# RC.net
KiCad netlist of a schematic drawn in EAGLE
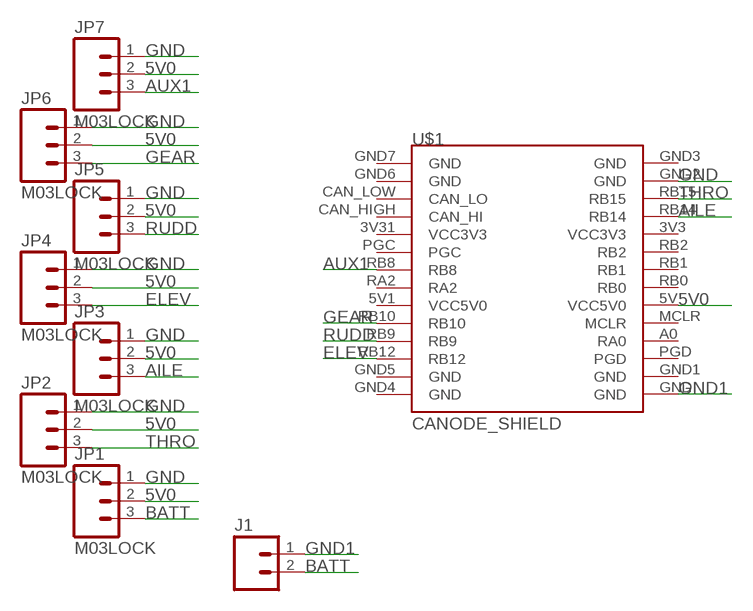
[diagram p0: schematic, sheet 1]

(export (version "E")
  (design (tool "Eeschema 10.0.6"))
  (components
    (comp (ref "J1")
      (value "M02LOCK")
      (footprint "eagle-import:1X02_LOCK")
      (libsource (lib "eagle-import") (part "M02LOCK"))
    )
    (comp (ref "JP1")
      (value "M03LOCK")
      (footprint "eagle-import:1X03_LOCK")
      (libsource (lib "eagle-import") (part "M03LOCK"))
    )
    (comp (ref "JP2")
      (value "M03LOCK")
      (footprint "eagle-import:1X03_LOCK")
      (libsource (lib "eagle-import") (part "M03LOCK"))
    )
    (comp (ref "JP3")
      (value "M03LOCK")
      (footprint "eagle-import:1X03_LOCK")
      (libsource (lib "eagle-import") (part "M03LOCK"))
    )
    (comp (ref "JP4")
      (value "M03LOCK")
      (footprint "eagle-import:1X03_LOCK")
      (libsource (lib "eagle-import") (part "M03LOCK"))
    )
    (comp (ref "JP5")
      (value "M03LOCK")
      (footprint "eagle-import:1X03_LOCK")
      (libsource (lib "eagle-import") (part "M03LOCK"))
    )
    (comp (ref "JP6")
      (value "M03LOCK")
      (footprint "eagle-import:1X03_LOCK")
      (libsource (lib "eagle-import") (part "M03LOCK"))
    )
    (comp (ref "JP7")
      (value "M03LOCK")
      (footprint "eagle-import:1X03_LOCK")
      (libsource (lib "eagle-import") (part "M03LOCK"))
    )
    (comp (ref "U$1")
      (value "CANODE_SHIELD")
      (footprint "eagle-import:CANODE_SHIELD")
      (libsource (lib "eagle-import") (part "CANODE_SHIELD"))
    )
  )
  (nets
    (net (code "1") (name "/5V0") (class "Default")
      (node (ref "JP1") (pin "2") (pinfunction "2_2") (pintype "passive"))
      (node (ref "JP2") (pin "2") (pinfunction "2_2") (pintype "passive"))
      (node (ref "JP3") (pin "2") (pinfunction "2_2") (pintype "passive"))
      (node (ref "JP4") (pin "2") (pinfunction "2_2") (pintype "passive"))
      (node (ref "JP5") (pin "2") (pinfunction "2_2") (pintype "passive"))
      (node (ref "JP6") (pin "2") (pinfunction "2_2") (pintype "passive"))
      (node (ref "JP7") (pin "2") (pinfunction "2_2") (pintype "passive"))
      (node (ref "U$1") (pin "5V") (pinfunction "VCC5V0_5V") (pintype "bidirectional"))
    )
    (net (code "2") (name "/AILE") (class "Default")
      (node (ref "JP3") (pin "3") (pinfunction "3_3") (pintype "passive"))
      (node (ref "U$1") (pin "RB14") (pinfunction "RB14_RB14") (pintype "bidirectional"))
    )
    (net (code "3") (name "/AUX1") (class "Default")
      (node (ref "JP7") (pin "3") (pinfunction "3_3") (pintype "passive"))
      (node (ref "U$1") (pin "RB8") (pinfunction "RB8_RB8") (pintype "bidirectional"))
    )
    (net (code "4") (name "/BATT") (class "Default")
      (node (ref "J1") (pin "2") (pinfunction "1_2") (pintype "passive"))
      (node (ref "JP1") (pin "3") (pinfunction "3_3") (pintype "passive"))
    )
    (net (code "5") (name "/ELEV") (class "Default")
      (node (ref "JP4") (pin "3") (pinfunction "3_3") (pintype "passive"))
      (node (ref "U$1") (pin "RB12") (pinfunction "RB12_RB12") (pintype "bidirectional"))
    )
    (net (code "6") (name "/GEAR") (class "Default")
      (node (ref "JP6") (pin "3") (pinfunction "3_3") (pintype "passive"))
      (node (ref "U$1") (pin "RB10") (pinfunction "RB10_RB10") (pintype "bidirectional"))
    )
    (net (code "7") (name "/GND") (class "Default")
      (node (ref "JP1") (pin "1") (pinfunction "1_1") (pintype "passive"))
      (node (ref "JP2") (pin "1") (pinfunction "1_1") (pintype "passive"))
      (node (ref "JP3") (pin "1") (pinfunction "1_1") (pintype "passive"))
      (node (ref "JP4") (pin "1") (pinfunction "1_1") (pintype "passive"))
      (node (ref "JP5") (pin "1") (pinfunction "1_1") (pintype "passive"))
      (node (ref "JP6") (pin "1") (pinfunction "1_1") (pintype "passive"))
      (node (ref "JP7") (pin "1") (pinfunction "1_1") (pintype "passive"))
      (node (ref "U$1") (pin "GND2") (pinfunction "GND_GND2") (pintype "bidirectional"))
    )
    (net (code "8") (name "/GND1") (class "Default")
      (node (ref "J1") (pin "1") (pinfunction "2_1") (pintype "passive"))
      (node (ref "U$1") (pin "GND") (pinfunction "GND_GND") (pintype "bidirectional"))
    )
    (net (code "9") (name "/RUDD") (class "Default")
      (node (ref "JP5") (pin "3") (pinfunction "3_3") (pintype "passive"))
      (node (ref "U$1") (pin "RB9") (pinfunction "RB9_RB9") (pintype "bidirectional"))
    )
    (net (code "10") (name "/THRO") (class "Default")
      (node (ref "JP2") (pin "3") (pinfunction "3_3") (pintype "passive"))
      (node (ref "U$1") (pin "RB15") (pinfunction "RB15_RB15") (pintype "bidirectional"))
    )
    (net (code "11") (name "unconnected-(U$1-CAN_HI-PadCAN_HIGH)") (class "Default")
      (node (ref "U$1") (pin "CAN_HIGH") (pinfunction "CAN_HI_CAN_HIGH") (pintype "bidirectional"))
    )
    (net (code "12") (name "unconnected-(U$1-CAN_LO-PadCAN_LOW)") (class "Default")
      (node (ref "U$1") (pin "CAN_LOW") (pinfunction "CAN_LO_CAN_LOW") (pintype "bidirectional"))
    )
    (net (code "13") (name "unconnected-(U$1-GND-PadGND1)") (class "Default")
      (node (ref "U$1") (pin "GND1") (pinfunction "GND_GND1") (pintype "bidirectional"))
    )
    (net (code "14") (name "unconnected-(U$1-GND-PadGND3)") (class "Default")
      (node (ref "U$1") (pin "GND3") (pinfunction "GND_GND3") (pintype "bidirectional"))
    )
    (net (code "15") (name "unconnected-(U$1-GND-PadGND4)") (class "Default")
      (node (ref "U$1") (pin "GND4") (pinfunction "GND_GND4") (pintype "bidirectional"))
    )
    (net (code "16") (name "unconnected-(U$1-GND-PadGND5)") (class "Default")
      (node (ref "U$1") (pin "GND5") (pinfunction "GND_GND5") (pintype "bidirectional"))
    )
    (net (code "17") (name "unconnected-(U$1-GND-PadGND6)") (class "Default")
      (node (ref "U$1") (pin "GND6") (pinfunction "GND_GND6") (pintype "bidirectional"))
    )
    (net (code "18") (name "unconnected-(U$1-GND-PadGND7)") (class "Default")
      (node (ref "U$1") (pin "GND7") (pinfunction "GND_GND7") (pintype "bidirectional"))
    )
    (net (code "19") (name "unconnected-(U$1-PadMCLR)") (class "Default")
      (node (ref "U$1") (pin "MCLR") (pinfunction "MCLR_MCLR") (pintype "bidirectional"))
    )
    (net (code "20") (name "unconnected-(U$1-PadPGC)") (class "Default")
      (node (ref "U$1") (pin "PGC") (pinfunction "PGC_PGC") (pintype "bidirectional"))
    )
    (net (code "21") (name "unconnected-(U$1-PadPGD)") (class "Default")
      (node (ref "U$1") (pin "PGD") (pinfunction "PGD_PGD") (pintype "bidirectional"))
    )
    (net (code "22") (name "unconnected-(U$1-PadRA2)") (class "Default")
      (node (ref "U$1") (pin "RA2") (pinfunction "RA2_RA2") (pintype "bidirectional"))
    )
    (net (code "23") (name "unconnected-(U$1-PadRB0)") (class "Default")
      (node (ref "U$1") (pin "RB0") (pinfunction "RB0_RB0") (pintype "bidirectional"))
    )
    (net (code "24") (name "unconnected-(U$1-PadRB1)") (class "Default")
      (node (ref "U$1") (pin "RB1") (pinfunction "RB1_RB1") (pintype "bidirectional"))
    )
    (net (code "25") (name "unconnected-(U$1-PadRB2)") (class "Default")
      (node (ref "U$1") (pin "RB2") (pinfunction "RB2_RB2") (pintype "bidirectional"))
    )
    (net (code "26") (name "unconnected-(U$1-RA0-PadA0)") (class "Default")
      (node (ref "U$1") (pin "A0") (pinfunction "RA0_A0") (pintype "bidirectional"))
    )
    (net (code "27") (name "unconnected-(U$1-VCC3V3-Pad3V3)") (class "Default")
      (node (ref "U$1") (pin "3V3") (pinfunction "VCC3V3_3V3") (pintype "bidirectional"))
    )
    (net (code "28") (name "unconnected-(U$1-VCC3V3-Pad3V31)") (class "Default")
      (node (ref "U$1") (pin "3V31") (pinfunction "VCC3V3_3V31") (pintype "bidirectional"))
    )
    (net (code "29") (name "unconnected-(U$1-VCC5V0-Pad5V1)") (class "Default")
      (node (ref "U$1") (pin "5V1") (pinfunction "VCC5V0_5V1") (pintype "bidirectional"))
    )
  )
)
